# ltk-hall_main_tc_heater.net
KiCad netlist of a schematic drawn in Altium Designer
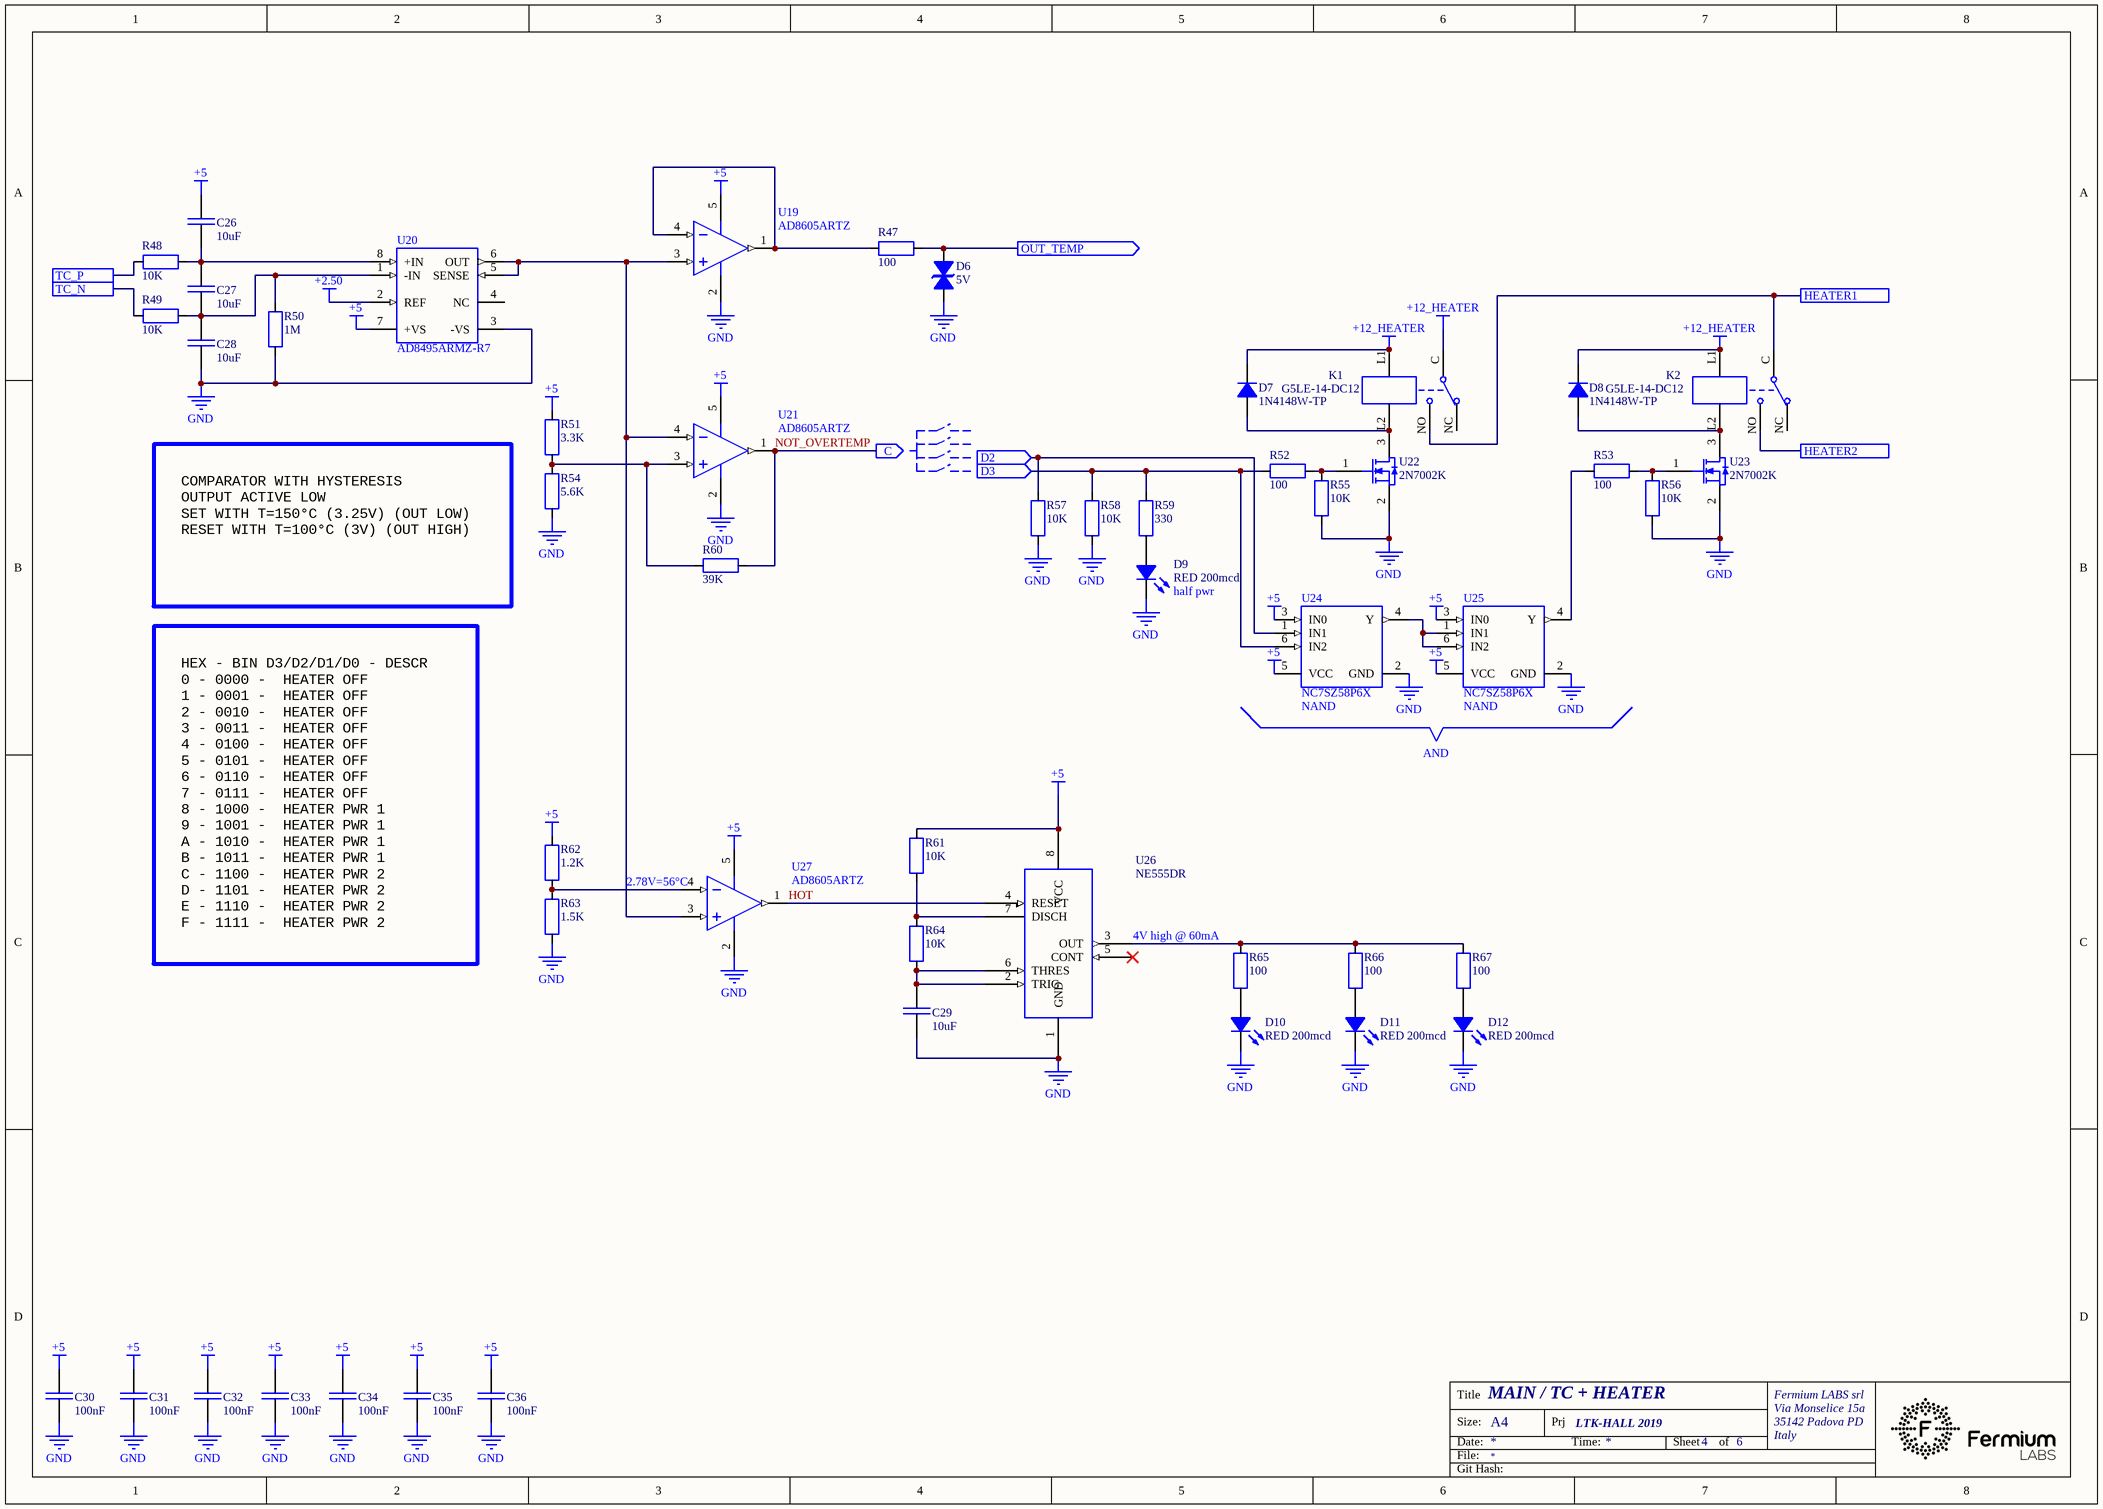
[diagram p0: ltk-hall_main_tc_heater.SchDoc]

(export (version "E")
  (design (tool "Eeschema 10.0.6"))
  (components
    (comp (ref "C26")
      (value "10uF")
      (footprint "CAP 0805_2012")
      (description "CAP SMD MLCC 10uF 25V 0805 X5R")
      (fields (field (name "PART NUMBER") "1ffbe5a9-0884-4740-bdad-20a6a98400e6"))
      (libsource (lib "frmdblib") (part "GENERIC_C"))
    )
    (comp (ref "C27")
      (value "10uF")
      (footprint "CAP 0805_2012")
      (description "CAP SMD MLCC 10uF 25V 0805 X5R")
      (fields (field (name "PART NUMBER") "1ffbe5a9-0884-4740-bdad-20a6a98400e6"))
      (libsource (lib "frmdblib") (part "GENERIC_C"))
    )
    (comp (ref "C28")
      (value "10uF")
      (footprint "CAP 0805_2012")
      (description "CAP SMD MLCC 10uF 25V 0805 X5R")
      (fields (field (name "PART NUMBER") "1ffbe5a9-0884-4740-bdad-20a6a98400e6"))
      (libsource (lib "frmdblib") (part "GENERIC_C"))
    )
    (comp (ref "C29")
      (value "10uF")
      (footprint "CAP 0805_2012")
      (description "CAP SMD MLCC 10uF 25V 0805 X5R")
      (fields (field (name "PART NUMBER") "1ffbe5a9-0884-4740-bdad-20a6a98400e6"))
      (libsource (lib "frmdblib") (part "GENERIC_C"))
    )
    (comp (ref "C30")
      (value "100nF")
      (footprint "CAP 0603_1608")
      (description "CAP SMD MLCC 100nF 25V 0603 X7R")
      (fields (field (name "PART NUMBER") "02841f84-ac15-41b5-9e17-915f8f067828"))
      (libsource (lib "frmdblib") (part "GENERIC_C"))
    )
    (comp (ref "C31")
      (value "100nF")
      (footprint "CAP 0603_1608")
      (description "CAP SMD MLCC 100nF 25V 0603 X7R")
      (fields (field (name "PART NUMBER") "02841f84-ac15-41b5-9e17-915f8f067828"))
      (libsource (lib "frmdblib") (part "GENERIC_C"))
    )
    (comp (ref "C32")
      (value "100nF")
      (footprint "CAP 0603_1608")
      (description "CAP SMD MLCC 100nF 25V 0603 X7R")
      (fields (field (name "PART NUMBER") "02841f84-ac15-41b5-9e17-915f8f067828"))
      (libsource (lib "frmdblib") (part "GENERIC_C"))
    )
    (comp (ref "C33")
      (value "100nF")
      (footprint "CAP 0603_1608")
      (description "CAP SMD MLCC 100nF 25V 0603 X7R")
      (fields (field (name "PART NUMBER") "02841f84-ac15-41b5-9e17-915f8f067828"))
      (libsource (lib "frmdblib") (part "GENERIC_C"))
    )
    (comp (ref "C34")
      (value "100nF")
      (footprint "CAP 0603_1608")
      (description "CAP SMD MLCC 100nF 25V 0603 X7R")
      (fields (field (name "PART NUMBER") "02841f84-ac15-41b5-9e17-915f8f067828"))
      (libsource (lib "frmdblib") (part "GENERIC_C"))
    )
    (comp (ref "C35")
      (value "100nF")
      (footprint "CAP 0603_1608")
      (description "CAP SMD MLCC 100nF 25V 0603 X7R")
      (fields (field (name "PART NUMBER") "02841f84-ac15-41b5-9e17-915f8f067828"))
      (libsource (lib "frmdblib") (part "GENERIC_C"))
    )
    (comp (ref "C36")
      (value "100nF")
      (footprint "CAP 0603_1608")
      (description "CAP SMD MLCC 100nF 25V 0603 X7R")
      (fields (field (name "PART NUMBER") "02841f84-ac15-41b5-9e17-915f8f067828"))
      (libsource (lib "frmdblib") (part "GENERIC_C"))
    )
    (comp (ref "D6")
      (value "5V")
      (footprint "SOD523F")
      (description "DIODE SMD TVS 5V BIDIRECTIONAL SOD-523")
      (fields (field (name "PART NUMBER") "daa58212-38e2-4326-a156-8e48058c46f1"))
      (libsource (lib "frmdblib") (part "GENERIC_D_TVS_BI"))
    )
    (comp (ref "D7")
      (value "1N4148W-TP")
      (footprint "SOD-123")
      (description "DIODE SMD 100V 150mA 1.5Vf SOD-123 4148")
      (fields (field (name "PART NUMBER") "5e920700-75df-48e3-84dd-8f9f777caed8"))
      (libsource (lib "frmdblib") (part "GENERIC_D"))
    )
    (comp (ref "D8")
      (value "1N4148W-TP")
      (footprint "SOD-123")
      (description "DIODE SMD 100V 150mA 1.5Vf SOD-123 4148")
      (fields (field (name "PART NUMBER") "5e920700-75df-48e3-84dd-8f9f777caed8"))
      (libsource (lib "frmdblib") (part "GENERIC_D"))
    )
    (comp (ref "D9")
      (value "RED 200mcd")
      (footprint "ED49B4F6-595F-4D62-96BB-D7184CAA9B94")
      (description "DIODE LED THT 5MM RED 200mcd")
      (fields (field (name "PART NUMBER") "c65ae3d2-9539-4634-8979-616a331b7494"))
      (libsource (lib "frmdblib") (part "GENERIC_D_LED"))
    )
    (comp (ref "D10")
      (value "RED 200mcd")
      (footprint "ED49B4F6-595F-4D62-96BB-D7184CAA9B94")
      (description "DIODE LED THT 5MM RED 200mcd")
      (fields (field (name "PART NUMBER") "c65ae3d2-9539-4634-8979-616a331b7494"))
      (libsource (lib "frmdblib") (part "GENERIC_D_LED"))
    )
    (comp (ref "D11")
      (value "RED 200mcd")
      (footprint "ED49B4F6-595F-4D62-96BB-D7184CAA9B94")
      (description "DIODE LED THT 5MM RED 200mcd")
      (fields (field (name "PART NUMBER") "c65ae3d2-9539-4634-8979-616a331b7494"))
      (libsource (lib "frmdblib") (part "GENERIC_D_LED"))
    )
    (comp (ref "D12")
      (value "RED 200mcd")
      (footprint "ED49B4F6-595F-4D62-96BB-D7184CAA9B94")
      (description "DIODE LED THT 5MM RED 200mcd")
      (fields (field (name "PART NUMBER") "c65ae3d2-9539-4634-8979-616a331b7494"))
      (libsource (lib "frmdblib") (part "GENERIC_D_LED"))
    )
    (comp (ref "K1")
      (value "G5LE-14-DC12")
      (footprint "AAE46D0F-8D2F-4914-8614-C04E242B4758")
      (description "RELAY SPDT 10A 250VAC 12VDC SUBMINIATURE")
      (fields (field (name "PART NUMBER") "daf6f3cd-58c4-4886-bcb7-b7b47a76ae08"))
      (libsource (lib "frmdblib") (part "GENERIC_RELAY_SPDT"))
    )
    (comp (ref "K2")
      (value "G5LE-14-DC12")
      (footprint "AAE46D0F-8D2F-4914-8614-C04E242B4758")
      (description "RELAY SPDT 10A 250VAC 12VDC SUBMINIATURE")
      (fields (field (name "PART NUMBER") "daf6f3cd-58c4-4886-bcb7-b7b47a76ae08"))
      (libsource (lib "frmdblib") (part "GENERIC_RELAY_SPDT"))
    )
    (comp (ref "R47")
      (value "100")
      (footprint "RES 0603_1608")
      (description "RES SMD 100 OHM 1% 1/10W 0603")
      (fields (field (name "PART NUMBER") "0a6c4b74-f837-4563-b154-6e196d753525"))
      (libsource (lib "frmdblib") (part "GENERIC_R"))
    )
    (comp (ref "R48")
      (value "10K")
      (footprint "RES 0603_1608")
      (description "RES SMD 10K OHM 1% 1/10W 0603")
      (fields (field (name "PART NUMBER") "93242766-ba1d-462d-b58f-ce1dfc4129c8"))
      (libsource (lib "frmdblib") (part "GENERIC_R"))
    )
    (comp (ref "R49")
      (value "10K")
      (footprint "RES 0603_1608")
      (description "RES SMD 10K OHM 1% 1/10W 0603")
      (fields (field (name "PART NUMBER") "93242766-ba1d-462d-b58f-ce1dfc4129c8"))
      (libsource (lib "frmdblib") (part "GENERIC_R"))
    )
    (comp (ref "R50")
      (value "1M")
      (footprint "RES 0603_1608")
      (description "RES SMD 1M OHM 1% 1/10W 0603")
      (fields (field (name "PART NUMBER") "99181d84-3ebc-4ea4-8625-26dc8592276c"))
      (libsource (lib "frmdblib") (part "GENERIC_R"))
    )
    (comp (ref "R51")
      (value "3.3K")
      (footprint "RES 0603_1608")
      (description "RES SMD 3.3K OHM 1% 1/10W 0603")
      (fields (field (name "PART NUMBER") "c685e076-af25-4fed-81c8-3eb7c43f01b8"))
      (libsource (lib "frmdblib") (part "GENERIC_R"))
    )
    (comp (ref "R52")
      (value "100")
      (footprint "RES 0603_1608")
      (description "RES SMD 100 OHM 1% 1/10W 0603")
      (fields (field (name "PART NUMBER") "0a6c4b74-f837-4563-b154-6e196d753525"))
      (libsource (lib "frmdblib") (part "GENERIC_R"))
    )
    (comp (ref "R53")
      (value "100")
      (footprint "RES 0603_1608")
      (description "RES SMD 100 OHM 1% 1/10W 0603")
      (fields (field (name "PART NUMBER") "0a6c4b74-f837-4563-b154-6e196d753525"))
      (libsource (lib "frmdblib") (part "GENERIC_R"))
    )
    (comp (ref "R54")
      (value "5.6K")
      (footprint "RES 0603_1608")
      (description "RES SMD 5.6K OHM 1% 1/10W 0603")
      (fields (field (name "PART NUMBER") "afc45e5f-a770-4ee7-b734-99356076b47f"))
      (libsource (lib "frmdblib") (part "GENERIC_R"))
    )
    (comp (ref "R55")
      (value "10K")
      (footprint "RES 0603_1608")
      (description "RES SMD 10K OHM 1% 1/10W 0603")
      (fields (field (name "PART NUMBER") "93242766-ba1d-462d-b58f-ce1dfc4129c8"))
      (libsource (lib "frmdblib") (part "GENERIC_R"))
    )
    (comp (ref "R56")
      (value "10K")
      (footprint "RES 0603_1608")
      (description "RES SMD 10K OHM 1% 1/10W 0603")
      (fields (field (name "PART NUMBER") "93242766-ba1d-462d-b58f-ce1dfc4129c8"))
      (libsource (lib "frmdblib") (part "GENERIC_R"))
    )
    (comp (ref "R57")
      (value "10K")
      (footprint "RES 0603_1608")
      (description "RES SMD 10K OHM 1% 1/10W 0603")
      (fields (field (name "PART NUMBER") "93242766-ba1d-462d-b58f-ce1dfc4129c8"))
      (libsource (lib "frmdblib") (part "GENERIC_R"))
    )
    (comp (ref "R58")
      (value "10K")
      (footprint "RES 0603_1608")
      (description "RES SMD 10K OHM 1% 1/10W 0603")
      (fields (field (name "PART NUMBER") "93242766-ba1d-462d-b58f-ce1dfc4129c8"))
      (libsource (lib "frmdblib") (part "GENERIC_R"))
    )
    (comp (ref "R59")
      (value "330")
      (footprint "RES 0603_1608")
      (description "RES SMD 330 OHM 1% 1/10W 0603")
      (fields (field (name "PART NUMBER") "e8555d7b-eeda-4727-b2e1-550cdc03d819"))
      (libsource (lib "frmdblib") (part "GENERIC_R"))
    )
    (comp (ref "R60")
      (value "39K")
      (footprint "RES 0603_1608")
      (description "RES SMD 39K OHM 1% 1/10W 0603")
      (fields (field (name "PART NUMBER") "10a824dc-98f1-41df-91f2-219e0508d035"))
      (libsource (lib "frmdblib") (part "GENERIC_R"))
    )
    (comp (ref "R61")
      (value "10K")
      (footprint "RES 0603_1608")
      (description "RES SMD 10K OHM 1% 1/10W 0603")
      (fields (field (name "PART NUMBER") "93242766-ba1d-462d-b58f-ce1dfc4129c8"))
      (libsource (lib "frmdblib") (part "GENERIC_R"))
    )
    (comp (ref "R62")
      (value "1.2K")
      (footprint "RES 0603_1608")
      (description "RES SMD 1.2K OHM 1% 1/10W 0603")
      (fields (field (name "PART NUMBER") "2f6201d5-48c6-41ab-ab40-2cc6255291b8"))
      (libsource (lib "frmdblib") (part "GENERIC_R"))
    )
    (comp (ref "R63")
      (value "1.5K")
      (footprint "RES 0603_1608")
      (description "RES SMD 1.5K OHM 1% 1/10W 0603")
      (fields (field (name "PART NUMBER") "d098bc01-c90d-4b51-91ee-1d9d1ccd8970"))
      (libsource (lib "frmdblib") (part "GENERIC_R"))
    )
    (comp (ref "R64")
      (value "10K")
      (footprint "RES 0603_1608")
      (description "RES SMD 10K OHM 1% 1/10W 0603")
      (fields (field (name "PART NUMBER") "93242766-ba1d-462d-b58f-ce1dfc4129c8"))
      (libsource (lib "frmdblib") (part "GENERIC_R"))
    )
    (comp (ref "R65")
      (value "100")
      (footprint "RES 0603_1608")
      (description "RES SMD 100 OHM 1% 1/10W 0603")
      (fields (field (name "PART NUMBER") "0a6c4b74-f837-4563-b154-6e196d753525"))
      (libsource (lib "frmdblib") (part "GENERIC_R"))
    )
    (comp (ref "R66")
      (value "100")
      (footprint "RES 0603_1608")
      (description "RES SMD 100 OHM 1% 1/10W 0603")
      (fields (field (name "PART NUMBER") "0a6c4b74-f837-4563-b154-6e196d753525"))
      (libsource (lib "frmdblib") (part "GENERIC_R"))
    )
    (comp (ref "R67")
      (value "100")
      (footprint "RES 0603_1608")
      (description "RES SMD 100 OHM 1% 1/10W 0603")
      (fields (field (name "PART NUMBER") "0a6c4b74-f837-4563-b154-6e196d753525"))
      (libsource (lib "frmdblib") (part "GENERIC_R"))
    )
    (comp (ref "U19")
      (value "AD8605ARTZ")
      (footprint "A3DDA0BC-073E-4B18-9613-F713A7EC1E27")
      (description "IC OPAMP 65uV 1pA RRIO 5V 80mA SOT-23-5")
      (fields (field (name "PART NUMBER") "5610e9ea-bca8-49b2-8e5f-11409231f6a4"))
      (libsource (lib "frmdblib") (part "8096D751-9DCE-401B-B65E-AAEE0733EA70"))
    )
    (comp (ref "U20")
      (value "AD8495ARMZ-R7")
      (footprint "ANALOG MSOP-8 RM-8")
      (description "IC THERMOCOUPLE AMPLIFIER MSOP-8")
      (fields (field (name "PART NUMBER") "8cc7f909-42c7-4251-909a-43740f41a1ca"))
      (libsource (lib "frmdblib") (part "8E2A16B8-3194-4245-8B24-4BAEF980A7F4"))
    )
    (comp (ref "U21")
      (value "AD8605ARTZ")
      (footprint "A3DDA0BC-073E-4B18-9613-F713A7EC1E27")
      (description "IC OPAMP 65uV 1pA RRIO 5V 80mA SOT-23-5")
      (fields (field (name "PART NUMBER") "5610e9ea-bca8-49b2-8e5f-11409231f6a4"))
      (libsource (lib "frmdblib") (part "8096D751-9DCE-401B-B65E-AAEE0733EA70"))
    )
    (comp (ref "U22")
      (value "2N7002K")
      (footprint "ON SEMI SOT-23-3")
      (description "MOSFET N-CHANNEL LOGIC LEVEL 300mA 3ohm 60V ESD-PROT 2N7002K SOT-23")
      (fields (field (name "PART NUMBER") "3a318f0a-3b94-47d9-91d5-8fc0a2f410e8"))
      (libsource (lib "frmdblib") (part "GENERIC_N_MOSFET_GSD"))
    )
    (comp (ref "U23")
      (value "2N7002K")
      (footprint "ON SEMI SOT-23-3")
      (description "MOSFET N-CHANNEL LOGIC LEVEL 300mA 3ohm 60V ESD-PROT 2N7002K SOT-23")
      (fields (field (name "PART NUMBER") "3a318f0a-3b94-47d9-91d5-8fc0a2f410e8"))
      (libsource (lib "frmdblib") (part "GENERIC_N_MOSFET_GSD"))
    )
    (comp (ref "U24")
      (value "NC7SZ58P6X")
      (footprint "CF792C6F-51F3-4C59-9918-AD84EFC14FA6")
      (description "IC LOGIC PORT CONFIGURABLE AND, OR, NAND, NOR, XOR, BUFFER, NOT 8ns  74XX58 SC-70")
      (fields (field (name "PART NUMBER") "22da43c7-1950-42f4-bc93-10d9cca79b4d"))
      (libsource (lib "frmdblib") (part "77922C7C-4696-4818-A68A-CF4581C7C2E9"))
    )
    (comp (ref "U25")
      (value "NC7SZ58P6X")
      (footprint "CF792C6F-51F3-4C59-9918-AD84EFC14FA6")
      (description "IC LOGIC PORT CONFIGURABLE AND, OR, NAND, NOR, XOR, BUFFER, NOT 8ns  74XX58 SC-70")
      (fields (field (name "PART NUMBER") "22da43c7-1950-42f4-bc93-10d9cca79b4d"))
      (libsource (lib "frmdblib") (part "77922C7C-4696-4818-A68A-CF4581C7C2E9"))
    )
    (comp (ref "U26")
      (value "NE555DR")
      (footprint "TI SOIC-8 D")
      (description "IC SMD TIMER NE555 SOIC-8")
      (fields (field (name "PART NUMBER") "d16ab88a-2543-469a-8940-7b800b633548"))
      (libsource (lib "frmdblib") (part "3A1FF759-9FC3-4379-AD1F-76F749A75FB1"))
    )
    (comp (ref "U27")
      (value "AD8605ARTZ")
      (footprint "A3DDA0BC-073E-4B18-9613-F713A7EC1E27")
      (description "IC OPAMP 65uV 1pA RRIO 5V 80mA SOT-23-5")
      (fields (field (name "PART NUMBER") "5610e9ea-bca8-49b2-8e5f-11409231f6a4"))
      (libsource (lib "frmdblib") (part "8096D751-9DCE-401B-B65E-AAEE0733EA70"))
    )
  )
  (nets
    (net (code "1") (name "+2.50") (class "Default")
      (node (ref "U20") (pin "2") (pinfunction "REF_2") (pintype "input"))
    )
    (net (code "2") (name "+5") (class "Default")
      (node (ref "C26") (pin "2") (pintype "passive"))
      (node (ref "C30") (pin "1") (pintype "passive"))
      (node (ref "C31") (pin "1") (pintype "passive"))
      (node (ref "C32") (pin "1") (pintype "passive"))
      (node (ref "C33") (pin "1") (pintype "passive"))
      (node (ref "C34") (pin "1") (pintype "passive"))
      (node (ref "C35") (pin "1") (pintype "passive"))
      (node (ref "C36") (pin "1") (pintype "passive"))
      (node (ref "R51") (pin "2") (pintype "passive"))
      (node (ref "R61") (pin "2") (pintype "passive"))
      (node (ref "R62") (pin "2") (pintype "passive"))
      (node (ref "U19") (pin "5") (pinfunction "+V_5") (pintype "power_in"))
      (node (ref "U20") (pin "7") (pinfunction "+VS_7") (pintype "power_in"))
      (node (ref "U21") (pin "5") (pinfunction "+V_5") (pintype "power_in"))
      (node (ref "U24") (pin "3") (pinfunction "IN0_3") (pintype "input"))
      (node (ref "U24") (pin "5") (pinfunction "VCC_5") (pintype "power_in"))
      (node (ref "U25") (pin "3") (pinfunction "IN0_3") (pintype "input"))
      (node (ref "U25") (pin "5") (pinfunction "VCC_5") (pintype "power_in"))
      (node (ref "U26") (pin "8") (pinfunction "VCC_8") (pintype "power_in"))
      (node (ref "U27") (pin "5") (pinfunction "+V_5") (pintype "power_in"))
    )
    (net (code "3") (name "+12_HEATER") (class "Default")
      (node (ref "D7") (pin "1") (pinfunction "K_1") (pintype "passive"))
      (node (ref "D8") (pin "1") (pinfunction "K_1") (pintype "passive"))
      (node (ref "K1") (pin "C") (pinfunction "C_C") (pintype "passive"))
      (node (ref "K1") (pin "L1") (pinfunction "L1_L1") (pintype "passive"))
      (node (ref "K2") (pin "L1") (pinfunction "L1_L1") (pintype "passive"))
    )
    (net (code "4") (name "/D2") (class "Default")
      (node (ref "R57") (pin "2") (pintype "passive"))
      (node (ref "U24") (pin "1") (pinfunction "IN1_1") (pintype "input"))
    )
    (net (code "5") (name "/D3") (class "Default")
      (node (ref "R52") (pin "1") (pintype "passive"))
      (node (ref "R58") (pin "2") (pintype "passive"))
      (node (ref "R59") (pin "2") (pintype "passive"))
      (node (ref "U24") (pin "6") (pinfunction "IN2_6") (pintype "input"))
    )
    (net (code "6") (name "/HEATER1") (class "Default")
      (node (ref "K1") (pin "NO") (pinfunction "NO_NO") (pintype "passive"))
      (node (ref "K2") (pin "C") (pinfunction "C_C") (pintype "passive"))
    )
    (net (code "7") (name "/HEATER2") (class "Default")
      (node (ref "K2") (pin "NO") (pinfunction "NO_NO") (pintype "passive"))
    )
    (net (code "8") (name "/HOT") (class "Default")
      (node (ref "U26") (pin "4") (pinfunction "RESET_4") (pintype "input"))
      (node (ref "U27") (pin "1") (pinfunction "OUT_1") (pintype "output"))
    )
    (net (code "9") (name "/NOT_OVERTEMP") (class "Default")
      (node (ref "R60") (pin "2") (pintype "passive"))
      (node (ref "U21") (pin "1") (pinfunction "OUT_1") (pintype "output"))
    )
    (net (code "10") (name "/OUT_TEMP") (class "Default")
      (node (ref "D6") (pin "1") (pintype "passive"))
      (node (ref "R47") (pin "2") (pintype "passive"))
    )
    (net (code "11") (name "/TC_N") (class "Default") (node (ref "R49") (pin "2") (pintype "passive")))
    (net (code "12") (name "/TC_P") (class "Default") (node (ref "R48") (pin "2") (pintype "passive")))
    (net (code "13") (name "GND") (class "Default")
      (node (ref "C28") (pin "1") (pintype "passive"))
      (node (ref "C29") (pin "1") (pintype "passive"))
      (node (ref "C30") (pin "2") (pintype "passive"))
      (node (ref "C31") (pin "2") (pintype "passive"))
      (node (ref "C32") (pin "2") (pintype "passive"))
      (node (ref "C33") (pin "2") (pintype "passive"))
      (node (ref "C34") (pin "2") (pintype "passive"))
      (node (ref "C35") (pin "2") (pintype "passive"))
      (node (ref "C36") (pin "2") (pintype "passive"))
      (node (ref "D10") (pin "1") (pinfunction "K_1") (pintype "passive"))
      (node (ref "D11") (pin "1") (pinfunction "K_1") (pintype "passive"))
      (node (ref "D12") (pin "1") (pinfunction "K_1") (pintype "passive"))
      (node (ref "D6") (pin "2") (pintype "passive"))
      (node (ref "D9") (pin "1") (pinfunction "K_1") (pintype "passive"))
      (node (ref "R50") (pin "1") (pintype "passive"))
      (node (ref "R54") (pin "1") (pintype "passive"))
      (node (ref "R55") (pin "1") (pintype "passive"))
      (node (ref "R56") (pin "1") (pintype "passive"))
      (node (ref "R57") (pin "1") (pintype "passive"))
      (node (ref "R58") (pin "1") (pintype "passive"))
      (node (ref "R63") (pin "1") (pintype "passive"))
      (node (ref "U19") (pin "2") (pinfunction "-V_2") (pintype "power_in"))
      (node (ref "U20") (pin "3") (pinfunction "-VS_3") (pintype "power_in"))
      (node (ref "U21") (pin "2") (pinfunction "-V_2") (pintype "power_in"))
      (node (ref "U22") (pin "2") (pinfunction "S_2") (pintype "passive"))
      (node (ref "U23") (pin "2") (pinfunction "S_2") (pintype "passive"))
      (node (ref "U24") (pin "2") (pinfunction "GND_2") (pintype "power_in"))
      (node (ref "U25") (pin "2") (pinfunction "GND_2") (pintype "power_in"))
      (node (ref "U26") (pin "1") (pinfunction "GND_1") (pintype "power_in"))
      (node (ref "U27") (pin "2") (pinfunction "-V_2") (pintype "power_in"))
    )
    (net (code "14") (name "Net-(D7-A)") (class "Default")
      (node (ref "D7") (pin "2") (pinfunction "A_2") (pintype "passive"))
      (node (ref "K1") (pin "L2") (pinfunction "L2_L2") (pintype "passive"))
      (node (ref "U22") (pin "3") (pinfunction "D_3") (pintype "passive"))
    )
    (net (code "15") (name "Net-(D8-A)") (class "Default")
      (node (ref "D8") (pin "2") (pinfunction "A_2") (pintype "passive"))
      (node (ref "K2") (pin "L2") (pinfunction "L2_L2") (pintype "passive"))
      (node (ref "U23") (pin "3") (pinfunction "D_3") (pintype "passive"))
    )
    (net (code "16") (name "Net-(D9-A)") (class "Default")
      (node (ref "D9") (pin "2") (pinfunction "A_2") (pintype "passive"))
      (node (ref "R59") (pin "1") (pintype "passive"))
    )
    (net (code "17") (name "Net-(D10-A)") (class "Default")
      (node (ref "D10") (pin "2") (pinfunction "A_2") (pintype "passive"))
      (node (ref "R65") (pin "1") (pintype "passive"))
    )
    (net (code "18") (name "Net-(D11-A)") (class "Default")
      (node (ref "D11") (pin "2") (pinfunction "A_2") (pintype "passive"))
      (node (ref "R66") (pin "1") (pintype "passive"))
    )
    (net (code "19") (name "Net-(D12-A)") (class "Default")
      (node (ref "D12") (pin "2") (pinfunction "A_2") (pintype "passive"))
      (node (ref "R67") (pin "1") (pintype "passive"))
    )
    (net (code "20") (name "Net-(U19-+IN)") (class "Default")
      (node (ref "U19") (pin "3") (pinfunction "+IN_3") (pintype "input"))
      (node (ref "U20") (pin "5") (pinfunction "SENSE_5") (pintype "input"))
      (node (ref "U20") (pin "6") (pinfunction "OUT_6") (pintype "output"))
      (node (ref "U21") (pin "4") (pinfunction "-IN_4") (pintype "input"))
      (node (ref "U27") (pin "3") (pinfunction "+IN_3") (pintype "input"))
    )
    (net (code "21") (name "Net-(U19--IN)") (class "Default")
      (node (ref "R47") (pin "1") (pintype "passive"))
      (node (ref "U19") (pin "1") (pinfunction "OUT_1") (pintype "output"))
      (node (ref "U19") (pin "4") (pinfunction "-IN_4") (pintype "input"))
    )
    (net (code "22") (name "Net-(U20-+IN)") (class "Default")
      (node (ref "C26") (pin "1") (pintype "passive"))
      (node (ref "C27") (pin "2") (pintype "passive"))
      (node (ref "R48") (pin "1") (pintype "passive"))
      (node (ref "U20") (pin "8") (pinfunction "+IN_8") (pintype "input"))
    )
    (net (code "23") (name "Net-(U20--IN)") (class "Default")
      (node (ref "C27") (pin "1") (pintype "passive"))
      (node (ref "C28") (pin "2") (pintype "passive"))
      (node (ref "R49") (pin "1") (pintype "passive"))
      (node (ref "R50") (pin "2") (pintype "passive"))
      (node (ref "U20") (pin "1") (pinfunction "-IN_1") (pintype "input"))
    )
    (net (code "24") (name "Net-(U21-+IN)") (class "Default")
      (node (ref "R51") (pin "1") (pintype "passive"))
      (node (ref "R54") (pin "2") (pintype "passive"))
      (node (ref "R60") (pin "1") (pintype "passive"))
      (node (ref "U21") (pin "3") (pinfunction "+IN_3") (pintype "input"))
    )
    (net (code "25") (name "Net-(U22-G)") (class "Default")
      (node (ref "R52") (pin "2") (pintype "passive"))
      (node (ref "R55") (pin "2") (pintype "passive"))
      (node (ref "U22") (pin "1") (pinfunction "G_1") (pintype "passive"))
    )
    (net (code "26") (name "Net-(U23-G)") (class "Default")
      (node (ref "R53") (pin "2") (pintype "passive"))
      (node (ref "R56") (pin "2") (pintype "passive"))
      (node (ref "U23") (pin "1") (pinfunction "G_1") (pintype "passive"))
    )
    (net (code "27") (name "Net-(U24-Y)") (class "Default")
      (node (ref "U24") (pin "4") (pinfunction "Y_4") (pintype "output"))
      (node (ref "U25") (pin "1") (pinfunction "IN1_1") (pintype "input"))
      (node (ref "U25") (pin "6") (pinfunction "IN2_6") (pintype "input"))
    )
    (net (code "28") (name "Net-(U25-Y)") (class "Default")
      (node (ref "R53") (pin "1") (pintype "passive"))
      (node (ref "U25") (pin "4") (pinfunction "Y_4") (pintype "output"))
    )
    (net (code "29") (name "Net-(U26-DISCH)") (class "Default")
      (node (ref "R61") (pin "1") (pintype "passive"))
      (node (ref "R64") (pin "2") (pintype "passive"))
      (node (ref "U26") (pin "7") (pinfunction "DISCH_7") (pintype "passive"))
    )
    (net (code "30") (name "Net-(U26-OUT)") (class "Default")
      (node (ref "R65") (pin "2") (pintype "passive"))
      (node (ref "R66") (pin "2") (pintype "passive"))
      (node (ref "R67") (pin "2") (pintype "passive"))
      (node (ref "U26") (pin "3") (pinfunction "OUT_3") (pintype "output"))
    )
    (net (code "31") (name "Net-(U26-THRES)") (class "Default")
      (node (ref "C29") (pin "2") (pintype "passive"))
      (node (ref "R64") (pin "1") (pintype "passive"))
      (node (ref "U26") (pin "2") (pinfunction "TRIG_2") (pintype "input"))
      (node (ref "U26") (pin "6") (pinfunction "THRES_6") (pintype "input"))
    )
    (net (code "32") (name "Net-(U27--IN)") (class "Default")
      (node (ref "R62") (pin "1") (pintype "passive"))
      (node (ref "R63") (pin "2") (pintype "passive"))
      (node (ref "U27") (pin "4") (pinfunction "-IN_4") (pintype "input"))
    )
    (net (code "33") (name "unconnected-(K1-PadNC)") (class "Default")
      (node (ref "K1") (pin "NC") (pinfunction "NC_NC") (pintype "passive"))
    )
    (net (code "34") (name "unconnected-(K2-PadNC)") (class "Default")
      (node (ref "K2") (pin "NC") (pinfunction "NC_NC") (pintype "passive"))
    )
    (net (code "35") (name "unconnected-(U20-NC-Pad4)") (class "Default")
      (node (ref "U20") (pin "4") (pinfunction "NC_4") (pintype "passive"))
    )
    (net (code "36") (name "unconnected-(U26-CONT-Pad5)") (class "Default")
      (node (ref "U26") (pin "5") (pinfunction "CONT_5") (pintype "input+no_connect"))
    )
  )
)
